# DAP-Audio-1.net
KiCad netlist of a schematic drawn in Altium Designer
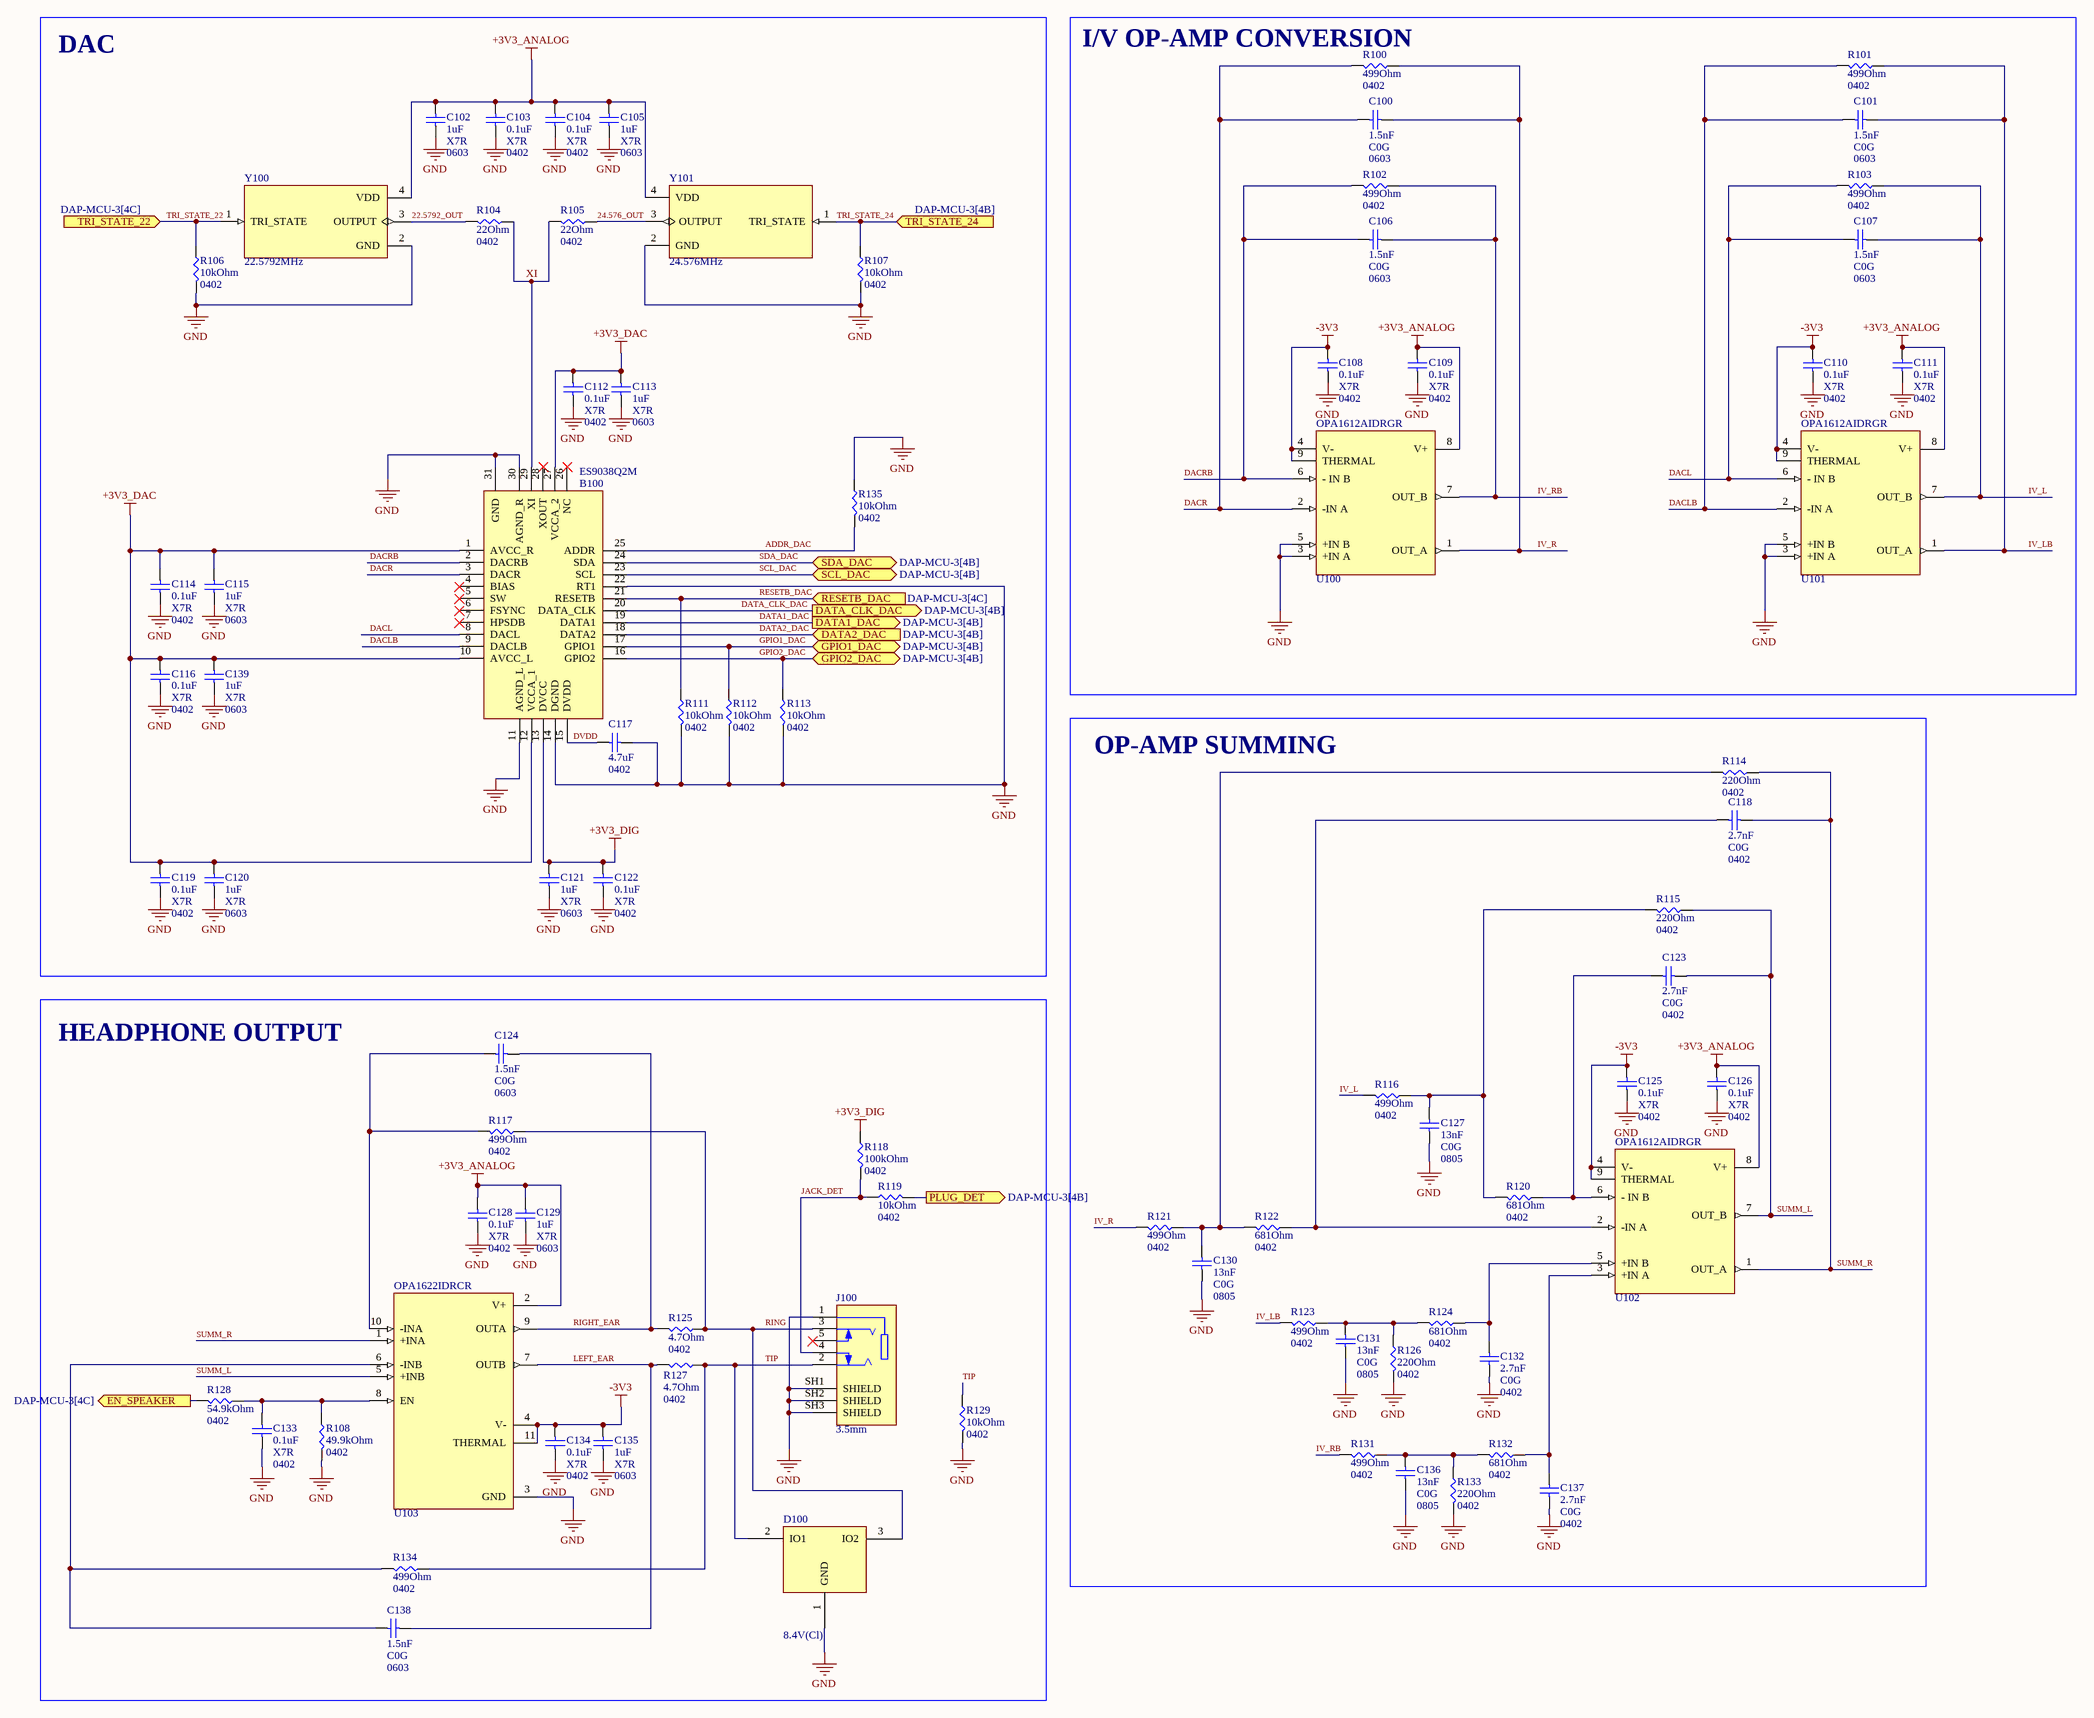
[diagram p0: DAP-Audio-1.SchDoc]

(export (version "E")
  (design (tool "Eeschema 10.0.6"))
  (components
    (comp (ref "B100")
      (value "DAC Audiophile")
      (footprint "QFN40P300X500X80-31N-D")
      (fields
        (field (name "MOUSER PART NUMBER") "460-ES9038Q2M")
        (field (name "MANUFACTURER_PART_NUMBER") "ES9038Q2M")
        (field (name "MANUFACTURER PART NUMBER 1") "ES9038Q2M")
        (field (name "CREATOR PROJECT") "DAP")
      )
      (libsource (lib "aloker-Link") (part "ES9038Q2M"))
    )
    (comp (ref "C100")
      (value "CAP CER 1500PF 50V C0G/NP0 0603")
      (footprint "CAPC1608X100N")
      (fields
        (field (name "<VALUE>") "1.5nF")
        (field (name "<SPEC>") "C0G")
        (field (name "<FOOTPRINT>") "0603")
        (field (name "CREATOR PROJECT") "DAP")
      )
      (libsource (lib "aloker-Link") (part "CAP"))
    )
    (comp (ref "C101")
      (value "CAP CER 1500PF 50V C0G/NP0 0603")
      (footprint "CAPC1608X100N")
      (fields
        (field (name "<VALUE>") "1.5nF")
        (field (name "<SPEC>") "C0G")
        (field (name "<FOOTPRINT>") "0603")
        (field (name "CREATOR PROJECT") "DAP")
      )
      (libsource (lib "aloker-Link") (part "CAP"))
    )
    (comp (ref "C102")
      (value "CAP CER 1UF 25V X7R 0603")
      (footprint "CAPC1608X100N")
      (fields
        (field (name "<VALUE>") "1uF")
        (field (name "<SPEC>") "X7R")
        (field (name "<FOOTPRINT>") "0603")
        (field (name "CREATOR PROJECT") "DAP")
      )
      (libsource (lib "aloker-Link") (part "CAP"))
    )
    (comp (ref "C103")
      (value "CAP CER 0.1UF 50V X7R 0402")
      (footprint "CAPC1005X60N")
      (fields
        (field (name "<VALUE>") "0.1uF")
        (field (name "<SPEC>") "X7R")
        (field (name "<FOOTPRINT>") "0402")
        (field (name "CREATOR PROJECT") "DAP")
      )
      (libsource (lib "aloker-Link") (part "CAP"))
    )
    (comp (ref "C104")
      (value "CAP CER 0.1UF 50V X7R 0402")
      (footprint "CAPC1005X60N")
      (fields
        (field (name "<VALUE>") "0.1uF")
        (field (name "<SPEC>") "X7R")
        (field (name "<FOOTPRINT>") "0402")
        (field (name "CREATOR PROJECT") "DAP")
      )
      (libsource (lib "aloker-Link") (part "CAP"))
    )
    (comp (ref "C105")
      (value "CAP CER 1UF 25V X7R 0603")
      (footprint "CAPC1608X100N")
      (fields
        (field (name "<VALUE>") "1uF")
        (field (name "<SPEC>") "X7R")
        (field (name "<FOOTPRINT>") "0603")
        (field (name "CREATOR PROJECT") "DAP")
      )
      (libsource (lib "aloker-Link") (part "CAP"))
    )
    (comp (ref "C106")
      (value "CAP CER 1500PF 50V C0G/NP0 0603")
      (footprint "CAPC1608X100N")
      (fields
        (field (name "<VALUE>") "1.5nF")
        (field (name "<SPEC>") "C0G")
        (field (name "<FOOTPRINT>") "0603")
        (field (name "CREATOR PROJECT") "DAP")
      )
      (libsource (lib "aloker-Link") (part "CAP"))
    )
    (comp (ref "C107")
      (value "CAP CER 1500PF 50V C0G/NP0 0603")
      (footprint "CAPC1608X100N")
      (fields
        (field (name "<VALUE>") "1.5nF")
        (field (name "<SPEC>") "C0G")
        (field (name "<FOOTPRINT>") "0603")
        (field (name "CREATOR PROJECT") "DAP")
      )
      (libsource (lib "aloker-Link") (part "CAP"))
    )
    (comp (ref "C108")
      (value "CAP CER 0.1UF 50V X7R 0402")
      (footprint "CAPC1005X60N")
      (fields
        (field (name "<VALUE>") "0.1uF")
        (field (name "<SPEC>") "X7R")
        (field (name "<FOOTPRINT>") "0402")
        (field (name "CREATOR PROJECT") "DAP")
      )
      (libsource (lib "aloker-Link") (part "CAP"))
    )
    (comp (ref "C109")
      (value "CAP CER 0.1UF 50V X7R 0402")
      (footprint "CAPC1005X60N")
      (fields
        (field (name "<VALUE>") "0.1uF")
        (field (name "<SPEC>") "X7R")
        (field (name "<FOOTPRINT>") "0402")
        (field (name "CREATOR PROJECT") "DAP")
      )
      (libsource (lib "aloker-Link") (part "CAP"))
    )
    (comp (ref "C110")
      (value "CAP CER 0.1UF 50V X7R 0402")
      (footprint "CAPC1005X60N")
      (fields
        (field (name "<VALUE>") "0.1uF")
        (field (name "<SPEC>") "X7R")
        (field (name "<FOOTPRINT>") "0402")
        (field (name "CREATOR PROJECT") "DAP")
      )
      (libsource (lib "aloker-Link") (part "CAP"))
    )
    (comp (ref "C111")
      (value "CAP CER 0.1UF 50V X7R 0402")
      (footprint "CAPC1005X60N")
      (fields
        (field (name "<VALUE>") "0.1uF")
        (field (name "<SPEC>") "X7R")
        (field (name "<FOOTPRINT>") "0402")
        (field (name "CREATOR PROJECT") "DAP")
      )
      (libsource (lib "aloker-Link") (part "CAP"))
    )
    (comp (ref "C112")
      (value "CAP CER 0.1UF 50V X7R 0402")
      (footprint "CAPC1005X60N")
      (fields
        (field (name "<VALUE>") "0.1uF")
        (field (name "<SPEC>") "X7R")
        (field (name "<FOOTPRINT>") "0402")
        (field (name "CREATOR PROJECT") "DAP")
      )
      (libsource (lib "aloker-Link") (part "CAP"))
    )
    (comp (ref "C113")
      (value "CAP CER 1UF 25V X7R 0603")
      (footprint "CAPC1608X100N")
      (fields
        (field (name "<VALUE>") "1uF")
        (field (name "<SPEC>") "X7R")
        (field (name "<FOOTPRINT>") "0603")
        (field (name "CREATOR PROJECT") "DAP")
      )
      (libsource (lib "aloker-Link") (part "CAP"))
    )
    (comp (ref "C114")
      (value "CAP CER 0.1UF 50V X7R 0402")
      (footprint "CAPC1005X60N")
      (fields
        (field (name "<VALUE>") "0.1uF")
        (field (name "<SPEC>") "X7R")
        (field (name "<FOOTPRINT>") "0402")
        (field (name "CREATOR PROJECT") "DAP")
      )
      (libsource (lib "aloker-Link") (part "CAP"))
    )
    (comp (ref "C115")
      (value "CAP CER 1UF 25V X7R 0603")
      (footprint "CAPC1608X100N")
      (fields
        (field (name "<VALUE>") "1uF")
        (field (name "<SPEC>") "X7R")
        (field (name "<FOOTPRINT>") "0603")
        (field (name "CREATOR PROJECT") "DAP")
      )
      (libsource (lib "aloker-Link") (part "CAP"))
    )
    (comp (ref "C116")
      (value "CAP CER 0.1UF 50V X7R 0402")
      (footprint "CAPC1005X60N")
      (fields
        (field (name "<VALUE>") "0.1uF")
        (field (name "<SPEC>") "X7R")
        (field (name "<FOOTPRINT>") "0402")
        (field (name "CREATOR PROJECT") "DAP")
      )
      (libsource (lib "aloker-Link") (part "CAP"))
    )
    (comp (ref "C117")
      (value "CAP CER 4.7UF 6.3V X5R 0402")
      (footprint "CAPC1005X60N")
      (fields
        (field (name "<VALUE>") "4.7uF")
        (field (name "<FOOTPRINT>") "0402")
        (field (name "CREATOR PROJECT") "DAP")
      )
      (libsource (lib "aloker-Link") (part "CAP"))
    )
    (comp (ref "C118")
      (value "CAP CER 2700PF 50V C0G/NP0 0402")
      (footprint "CAPC1005X60N")
      (fields
        (field (name "<VALUE>") "2.7nF")
        (field (name "<SPEC>") "C0G")
        (field (name "<FOOTPRINT>") "0402")
        (field (name "CREATOR PROJECT") "DAP")
      )
      (libsource (lib "aloker-Link") (part "CAP"))
    )
    (comp (ref "C119")
      (value "CAP CER 0.1UF 50V X7R 0402")
      (footprint "CAPC1005X60N")
      (fields
        (field (name "<VALUE>") "0.1uF")
        (field (name "<SPEC>") "X7R")
        (field (name "<FOOTPRINT>") "0402")
        (field (name "CREATOR PROJECT") "DAP")
      )
      (libsource (lib "aloker-Link") (part "CAP"))
    )
    (comp (ref "C120")
      (value "CAP CER 1UF 25V X7R 0603")
      (footprint "CAPC1608X100N")
      (fields
        (field (name "<VALUE>") "1uF")
        (field (name "<SPEC>") "X7R")
        (field (name "<FOOTPRINT>") "0603")
        (field (name "CREATOR PROJECT") "DAP")
      )
      (libsource (lib "aloker-Link") (part "CAP"))
    )
    (comp (ref "C121")
      (value "CAP CER 1UF 25V X7R 0603")
      (footprint "CAPC1608X100N")
      (fields
        (field (name "<VALUE>") "1uF")
        (field (name "<SPEC>") "X7R")
        (field (name "<FOOTPRINT>") "0603")
        (field (name "CREATOR PROJECT") "DAP")
      )
      (libsource (lib "aloker-Link") (part "CAP"))
    )
    (comp (ref "C122")
      (value "CAP CER 0.1UF 50V X7R 0402")
      (footprint "CAPC1005X60N")
      (fields
        (field (name "<VALUE>") "0.1uF")
        (field (name "<SPEC>") "X7R")
        (field (name "<FOOTPRINT>") "0402")
        (field (name "CREATOR PROJECT") "DAP")
      )
      (libsource (lib "aloker-Link") (part "CAP"))
    )
    (comp (ref "C123")
      (value "CAP CER 2700PF 50V C0G/NP0 0402")
      (footprint "CAPC1005X60N")
      (fields
        (field (name "<VALUE>") "2.7nF")
        (field (name "<SPEC>") "C0G")
        (field (name "<FOOTPRINT>") "0402")
        (field (name "CREATOR PROJECT") "DAP")
      )
      (libsource (lib "aloker-Link") (part "CAP"))
    )
    (comp (ref "C124")
      (value "CAP CER 1500PF 50V C0G/NP0 0603")
      (footprint "CAPC1608X100N")
      (fields
        (field (name "<VALUE>") "1.5nF")
        (field (name "<SPEC>") "C0G")
        (field (name "<FOOTPRINT>") "0603")
        (field (name "CREATOR PROJECT") "DAP")
      )
      (libsource (lib "aloker-Link") (part "CAP"))
    )
    (comp (ref "C125")
      (value "CAP CER 0.1UF 50V X7R 0402")
      (footprint "CAPC1005X60N")
      (fields
        (field (name "<VALUE>") "0.1uF")
        (field (name "<SPEC>") "X7R")
        (field (name "<FOOTPRINT>") "0402")
        (field (name "CREATOR PROJECT") "DAP")
      )
      (libsource (lib "aloker-Link") (part "CAP"))
    )
    (comp (ref "C126")
      (value "CAP CER 0.1UF 50V X7R 0402")
      (footprint "CAPC1005X60N")
      (fields
        (field (name "<VALUE>") "0.1uF")
        (field (name "<SPEC>") "X7R")
        (field (name "<FOOTPRINT>") "0402")
        (field (name "CREATOR PROJECT") "DAP")
      )
      (libsource (lib "aloker-Link") (part "CAP"))
    )
    (comp (ref "C127")
      (value "CAP CER 0.013UF 50V C0G/NP0 0805")
      (footprint "CAP_MUR_0805")
      (fields
        (field (name "<VALUE>") "13nF")
        (field (name "<SPEC>") "C0G")
        (field (name "<FOOTPRINT>") "0805")
        (field (name "CREATOR PROJECT") "DAP")
      )
      (libsource (lib "aloker-Link") (part "CAP"))
    )
    (comp (ref "C128")
      (value "CAP CER 0.1UF 50V X7R 0402")
      (footprint "CAPC1005X60N")
      (fields
        (field (name "<VALUE>") "0.1uF")
        (field (name "<SPEC>") "X7R")
        (field (name "<FOOTPRINT>") "0402")
        (field (name "CREATOR PROJECT") "DAP")
      )
      (libsource (lib "aloker-Link") (part "CAP"))
    )
    (comp (ref "C129")
      (value "CAP CER 1UF 25V X7R 0603")
      (footprint "CAPC1608X100N")
      (fields
        (field (name "<VALUE>") "1uF")
        (field (name "<SPEC>") "X7R")
        (field (name "<FOOTPRINT>") "0603")
        (field (name "CREATOR PROJECT") "DAP")
      )
      (libsource (lib "aloker-Link") (part "CAP"))
    )
    (comp (ref "C130")
      (value "CAP CER 0.013UF 50V C0G/NP0 0805")
      (footprint "CAP_MUR_0805")
      (fields
        (field (name "<VALUE>") "13nF")
        (field (name "<SPEC>") "C0G")
        (field (name "<FOOTPRINT>") "0805")
        (field (name "CREATOR PROJECT") "DAP")
      )
      (libsource (lib "aloker-Link") (part "CAP"))
    )
    (comp (ref "C131")
      (value "CAP CER 0.013UF 50V C0G/NP0 0805")
      (footprint "CAP_MUR_0805")
      (fields
        (field (name "<VALUE>") "13nF")
        (field (name "<SPEC>") "C0G")
        (field (name "<FOOTPRINT>") "0805")
        (field (name "CREATOR PROJECT") "DAP")
      )
      (libsource (lib "aloker-Link") (part "CAP"))
    )
    (comp (ref "C132")
      (value "CAP CER 2700PF 50V C0G/NP0 0402")
      (footprint "CAPC1005X60N")
      (fields
        (field (name "<VALUE>") "2.7nF")
        (field (name "<SPEC>") "C0G")
        (field (name "<FOOTPRINT>") "0402")
        (field (name "CREATOR PROJECT") "DAP")
      )
      (libsource (lib "aloker-Link") (part "CAP"))
    )
    (comp (ref "C133")
      (value "CAP CER 0.1UF 50V X7R 0402")
      (footprint "CAPC1005X60N")
      (fields
        (field (name "<VALUE>") "0.1uF")
        (field (name "<SPEC>") "X7R")
        (field (name "<FOOTPRINT>") "0402")
        (field (name "CREATOR PROJECT") "DAP")
      )
      (libsource (lib "aloker-Link") (part "CAP"))
    )
    (comp (ref "C134")
      (value "CAP CER 0.1UF 50V X7R 0402")
      (footprint "CAPC1005X60N")
      (fields
        (field (name "<VALUE>") "0.1uF")
        (field (name "<SPEC>") "X7R")
        (field (name "<FOOTPRINT>") "0402")
        (field (name "CREATOR PROJECT") "DAP")
      )
      (libsource (lib "aloker-Link") (part "CAP"))
    )
    (comp (ref "C135")
      (value "CAP CER 1UF 25V X7R 0603")
      (footprint "CAPC1608X100N")
      (fields
        (field (name "<VALUE>") "1uF")
        (field (name "<SPEC>") "X7R")
        (field (name "<FOOTPRINT>") "0603")
        (field (name "CREATOR PROJECT") "DAP")
      )
      (libsource (lib "aloker-Link") (part "CAP"))
    )
    (comp (ref "C136")
      (value "CAP CER 0.013UF 50V C0G/NP0 0805")
      (footprint "CAP_MUR_0805")
      (fields
        (field (name "<VALUE>") "13nF")
        (field (name "<SPEC>") "C0G")
        (field (name "<FOOTPRINT>") "0805")
        (field (name "CREATOR PROJECT") "DAP")
      )
      (libsource (lib "aloker-Link") (part "CAP"))
    )
    (comp (ref "C137")
      (value "CAP CER 2700PF 50V C0G/NP0 0402")
      (footprint "CAPC1005X60N")
      (fields
        (field (name "<VALUE>") "2.7nF")
        (field (name "<SPEC>") "C0G")
        (field (name "<FOOTPRINT>") "0402")
        (field (name "CREATOR PROJECT") "DAP")
      )
      (libsource (lib "aloker-Link") (part "CAP"))
    )
    (comp (ref "C138")
      (value "CAP CER 1500PF 50V C0G/NP0 0603")
      (footprint "CAPC1608X100N")
      (fields
        (field (name "<VALUE>") "1.5nF")
        (field (name "<SPEC>") "C0G")
        (field (name "<FOOTPRINT>") "0603")
        (field (name "CREATOR PROJECT") "DAP")
      )
      (libsource (lib "aloker-Link") (part "CAP"))
    )
    (comp (ref "C139")
      (value "CAP CER 1UF 25V X7R 0603")
      (footprint "CAPC1608X100N")
      (fields
        (field (name "<VALUE>") "1uF")
        (field (name "<SPEC>") "X7R")
        (field (name "<FOOTPRINT>") "0603")
        (field (name "CREATOR PROJECT") "DAP")
      )
      (libsource (lib "aloker-Link") (part "CAP"))
    )
    (comp (ref "D100")
      (value "TVS DIODE 3.6VWM 8.4VC 3X2SON")
      (footprint "IC_ESD122DMXR")
      (fields (field (name "<VALUE>") "8.4V(Cl)") (field (name "CREATOR PROJECT") "DAP"))
      (libsource (lib "aloker-Link") (part "TVS_DIODE_2BI"))
    )
    (comp (ref "J100")
      (value "CONN JACK STEREO 3.5MM R/A")
      (footprint "CUI_SJ1-3535NS")
      (fields
        (field (name "MF") "Same Sky")
        (field (name "MP") "SJ1-3535NS")
        (field (name "<VALUE>") "3.5mm")
        (field (name "CREATOR PROJECT") "DAP")
      )
      (libsource (lib "aloker-Link") (part "SJ1-3535NS"))
    )
    (comp (ref "R100")
      (value "RES SMD 499 OHM 0.1% 1/16W 0402")
      (footprint "RESC1005X40N")
      (fields
        (field (name "<VALUE>") "499Ohm")
        (field (name "<FOOTPRINT>") "0402")
        (field (name "CREATOR PROJECT") "DAP")
      )
      (libsource (lib "aloker-Link") (part "RES"))
    )
    (comp (ref "R101")
      (value "RES SMD 499 OHM 0.1% 1/16W 0402")
      (footprint "RESC1005X40N")
      (fields
        (field (name "<VALUE>") "499Ohm")
        (field (name "<FOOTPRINT>") "0402")
        (field (name "CREATOR PROJECT") "DAP")
      )
      (libsource (lib "aloker-Link") (part "RES"))
    )
    (comp (ref "R102")
      (value "RES SMD 499 OHM 0.1% 1/16W 0402")
      (footprint "RESC1005X40N")
      (fields
        (field (name "<VALUE>") "499Ohm")
        (field (name "<FOOTPRINT>") "0402")
        (field (name "CREATOR PROJECT") "DAP")
      )
      (libsource (lib "aloker-Link") (part "RES"))
    )
    (comp (ref "R103")
      (value "RES SMD 499 OHM 0.1% 1/16W 0402")
      (footprint "RESC1005X40N")
      (fields
        (field (name "<VALUE>") "499Ohm")
        (field (name "<FOOTPRINT>") "0402")
        (field (name "CREATOR PROJECT") "DAP")
      )
      (libsource (lib "aloker-Link") (part "RES"))
    )
    (comp (ref "R104")
      (value "RES 22 OHM 1% 1/16W 0402")
      (footprint "RESC1005X40N")
      (fields
        (field (name "<VALUE>") "22Ohm")
        (field (name "<FOOTPRINT>") "0402")
        (field (name "CREATOR PROJECT") "DAP")
      )
      (libsource (lib "aloker-Link") (part "RES"))
    )
    (comp (ref "R105")
      (value "RES 22 OHM 1% 1/16W 0402")
      (footprint "RESC1005X40N")
      (fields
        (field (name "<VALUE>") "22Ohm")
        (field (name "<FOOTPRINT>") "0402")
        (field (name "CREATOR PROJECT") "DAP")
      )
      (libsource (lib "aloker-Link") (part "RES"))
    )
    (comp (ref "R106")
      (value "RES SMD 10K OHM 1% 1/16W 0402")
      (footprint "RESC1005X40N")
      (fields
        (field (name "<VALUE>") "10kOhm")
        (field (name "<FOOTPRINT>") "0402")
        (field (name "CREATOR PROJECT") "DAP")
      )
      (libsource (lib "aloker-Link") (part "RES"))
    )
    (comp (ref "R107")
      (value "RES SMD 10K OHM 1% 1/16W 0402")
      (footprint "RESC1005X40N")
      (fields
        (field (name "<VALUE>") "10kOhm")
        (field (name "<FOOTPRINT>") "0402")
        (field (name "CREATOR PROJECT") "DAP")
      )
      (libsource (lib "aloker-Link") (part "RES"))
    )
    (comp (ref "R108")
      (value "RES SMD 49.9KOHM 0.1% 1/16W 0402")
      (footprint "RESC1005X40N")
      (fields
        (field (name "<VALUE>") "49.9kOhm")
        (field (name "<FOOTPRINT>") "0402")
        (field (name "CREATOR PROJECT") "DAP")
      )
      (libsource (lib "aloker-Link") (part "RES"))
    )
    (comp (ref "R111")
      (value "RES SMD 10K OHM 1% 1/16W 0402")
      (footprint "RESC1005X40N")
      (fields
        (field (name "<VALUE>") "10kOhm")
        (field (name "<FOOTPRINT>") "0402")
        (field (name "CREATOR PROJECT") "DAP")
      )
      (libsource (lib "aloker-Link") (part "RES"))
    )
    (comp (ref "R112")
      (value "RES SMD 10K OHM 1% 1/16W 0402")
      (footprint "RESC1005X40N")
      (fields
        (field (name "<VALUE>") "10kOhm")
        (field (name "<FOOTPRINT>") "0402")
        (field (name "CREATOR PROJECT") "DAP")
      )
      (libsource (lib "aloker-Link") (part "RES"))
    )
    (comp (ref "R113")
      (value "RES SMD 10K OHM 1% 1/16W 0402")
      (footprint "RESC1005X40N")
      (fields
        (field (name "<VALUE>") "10kOhm")
        (field (name "<FOOTPRINT>") "0402")
        (field (name "CREATOR PROJECT") "DAP")
      )
      (libsource (lib "aloker-Link") (part "RES"))
    )
    (comp (ref "R114")
      (value "RES SMD 220 OHM 0.1% 1/16W 0402")
      (footprint "RESC1005X40N")
      (fields
        (field (name "<VALUE>") "220Ohm")
        (field (name "<FOOTPRINT>") "0402")
        (field (name "CREATOR PROJECT") "DAP")
      )
      (libsource (lib "aloker-Link") (part "RES"))
    )
    (comp (ref "R115")
      (value "RES SMD 220 OHM 0.1% 1/16W 0402")
      (footprint "RESC1005X40N")
      (fields
        (field (name "<VALUE>") "220Ohm")
        (field (name "<FOOTPRINT>") "0402")
        (field (name "CREATOR PROJECT") "DAP")
      )
      (libsource (lib "aloker-Link") (part "RES"))
    )
    (comp (ref "R116")
      (value "RES SMD 499 OHM 0.1% 1/16W 0402")
      (footprint "RESC1005X40N")
      (fields
        (field (name "<VALUE>") "499Ohm")
        (field (name "<FOOTPRINT>") "0402")
        (field (name "CREATOR PROJECT") "DAP")
      )
      (libsource (lib "aloker-Link") (part "RES"))
    )
    (comp (ref "R117")
      (value "RES SMD 499 OHM 0.1% 1/16W 0402")
      (footprint "RESC1005X40N")
      (fields
        (field (name "<VALUE>") "499Ohm")
        (field (name "<FOOTPRINT>") "0402")
        (field (name "CREATOR PROJECT") "DAP")
      )
      (libsource (lib "aloker-Link") (part "RES"))
    )
    (comp (ref "R118")
      (value "RES SMD 100K OHM 0.1% 1/16W 0402")
      (footprint "RESC1005X40N")
      (fields
        (field (name "<VALUE>") "100kOhm")
        (field (name "<FOOTPRINT>") "0402")
        (field (name "CREATOR PROJECT") "DAP")
      )
      (libsource (lib "aloker-Link") (part "RES"))
    )
    (comp (ref "R119")
      (value "RES SMD 10K OHM 1% 1/16W 0402")
      (footprint "RESC1005X40N")
      (fields
        (field (name "<VALUE>") "10kOhm")
        (field (name "<FOOTPRINT>") "0402")
        (field (name "CREATOR PROJECT") "DAP")
      )
      (libsource (lib "aloker-Link") (part "RES"))
    )
    (comp (ref "R120")
      (value "RES SMD 681 OHM 0.1% 1/16W 0402")
      (footprint "RESC1005X40N")
      (fields
        (field (name "<VALUE>") "681Ohm")
        (field (name "<FOOTPRINT>") "0402")
        (field (name "CREATOR PROJECT") "DAP")
      )
      (libsource (lib "aloker-Link") (part "RES"))
    )
    (comp (ref "R121")
      (value "RES SMD 499 OHM 0.1% 1/16W 0402")
      (footprint "RESC1005X40N")
      (fields
        (field (name "<VALUE>") "499Ohm")
        (field (name "<FOOTPRINT>") "0402")
        (field (name "CREATOR PROJECT") "DAP")
      )
      (libsource (lib "aloker-Link") (part "RES"))
    )
    (comp (ref "R122")
      (value "RES SMD 681 OHM 0.1% 1/16W 0402")
      (footprint "RESC1005X40N")
      (fields
        (field (name "<VALUE>") "681Ohm")
        (field (name "<FOOTPRINT>") "0402")
        (field (name "CREATOR PROJECT") "DAP")
      )
      (libsource (lib "aloker-Link") (part "RES"))
    )
    (comp (ref "R123")
      (value "RES SMD 499 OHM 0.1% 1/16W 0402")
      (footprint "RESC1005X40N")
      (fields
        (field (name "<VALUE>") "499Ohm")
        (field (name "<FOOTPRINT>") "0402")
        (field (name "CREATOR PROJECT") "DAP")
      )
      (libsource (lib "aloker-Link") (part "RES"))
    )
    (comp (ref "R124")
      (value "RES SMD 681 OHM 0.1% 1/16W 0402")
      (footprint "RESC1005X40N")
      (fields
        (field (name "<VALUE>") "681Ohm")
        (field (name "<FOOTPRINT>") "0402")
        (field (name "CREATOR PROJECT") "DAP")
      )
      (libsource (lib "aloker-Link") (part "RES"))
    )
    (comp (ref "R125")
      (value "RES SMD 4.7 OHM 0.1% 1/16W 0402")
      (footprint "RESC1005X40N")
      (fields
        (field (name "<VALUE>") "4.7Ohm")
        (field (name "<FOOTPRINT>") "0402")
        (field (name "CREATOR PROJECT") "DAP")
      )
      (libsource (lib "aloker-Link") (part "RES"))
    )
    (comp (ref "R126")
      (value "RES SMD 220 OHM 0.1% 1/16W 0402")
      (footprint "RESC1005X40N")
      (fields
        (field (name "<VALUE>") "220Ohm")
        (field (name "<FOOTPRINT>") "0402")
        (field (name "CREATOR PROJECT") "DAP")
      )
      (libsource (lib "aloker-Link") (part "RES"))
    )
    (comp (ref "R127")
      (value "RES SMD 4.7 OHM 0.1% 1/16W 0402")
      (footprint "RESC1005X40N")
      (fields
        (field (name "<VALUE>") "4.7Ohm")
        (field (name "<FOOTPRINT>") "0402")
        (field (name "CREATOR PROJECT") "DAP")
      )
      (libsource (lib "aloker-Link") (part "RES"))
    )
    (comp (ref "R128")
      (value "RES SMD 54.9KOHM 0.1% 1/16W 0402")
      (footprint "RESC1005X40N")
      (fields
        (field (name "<VALUE>") "54.9kOhm")
        (field (name "<FOOTPRINT>") "0402")
        (field (name "CREATOR PROJECT") "DAP")
      )
      (libsource (lib "aloker-Link") (part "RES"))
    )
    (comp (ref "R129")
      (value "RES SMD 10K OHM 1% 1/16W 0402")
      (footprint "RESC1005X40N")
      (fields
        (field (name "<VALUE>") "10kOhm")
        (field (name "<FOOTPRINT>") "0402")
        (field (name "CREATOR PROJECT") "DAP")
      )
      (libsource (lib "aloker-Link") (part "RES"))
    )
    (comp (ref "R131")
      (value "RES SMD 499 OHM 0.1% 1/16W 0402")
      (footprint "RESC1005X40N")
      (fields
        (field (name "<VALUE>") "499Ohm")
        (field (name "<FOOTPRINT>") "0402")
        (field (name "CREATOR PROJECT") "DAP")
      )
      (libsource (lib "aloker-Link") (part "RES"))
    )
    (comp (ref "R132")
      (value "RES SMD 681 OHM 0.1% 1/16W 0402")
      (footprint "RESC1005X40N")
      (fields
        (field (name "<VALUE>") "681Ohm")
        (field (name "<FOOTPRINT>") "0402")
        (field (name "CREATOR PROJECT") "DAP")
      )
      (libsource (lib "aloker-Link") (part "RES"))
    )
    (comp (ref "R133")
      (value "RES SMD 220 OHM 0.1% 1/16W 0402")
      (footprint "RESC1005X40N")
      (fields
        (field (name "<VALUE>") "220Ohm")
        (field (name "<FOOTPRINT>") "0402")
        (field (name "CREATOR PROJECT") "DAP")
      )
      (libsource (lib "aloker-Link") (part "RES"))
    )
    (comp (ref "R134")
      (value "RES SMD 499 OHM 0.1% 1/16W 0402")
      (footprint "RESC1005X40N")
      (fields
        (field (name "<VALUE>") "499Ohm")
        (field (name "<FOOTPRINT>") "0402")
        (field (name "CREATOR PROJECT") "DAP")
      )
      (libsource (lib "aloker-Link") (part "RES"))
    )
    (comp (ref "R135")
      (value "RES SMD 10K OHM 1% 1/16W 0402")
      (footprint "RESC1005X40N")
      (fields
        (field (name "<VALUE>") "10kOhm")
        (field (name "<FOOTPRINT>") "0402")
        (field (name "CREATOR PROJECT") "DAP")
      )
      (libsource (lib "aloker-Link") (part "RES"))
    )
    (comp (ref "U100")
      (value "IC OP AMP 2CH 8-SON")
      (footprint "SON50P300X300X80-9N200X120")
      (fields
        (field (name "MANUFACTURER PART NUMBER 1") "OPA1612AIDRGR")
        (field (name "CREATOR PROJECT") "DAP")
      )
      (libsource (lib "aloker-Link") (part "OPA1612AIDRGR"))
    )
    (comp (ref "U101")
      (value "IC OP AMP 2CH 8-SON")
      (footprint "SON50P300X300X80-9N200X120")
      (fields
        (field (name "MANUFACTURER PART NUMBER 1") "OPA1612AIDRGR")
        (field (name "CREATOR PROJECT") "DAP")
      )
      (libsource (lib "aloker-Link") (part "OPA1612AIDRGR"))
    )
    (comp (ref "U102")
      (value "IC OP AMP 2CH 8-SON")
      (footprint "SON50P300X300X80-9N200X120")
      (fields
        (field (name "MANUFACTURER PART NUMBER 1") "OPA1612AIDRGR")
        (field (name "CREATOR PROJECT") "DAP")
      )
      (libsource (lib "aloker-Link") (part "OPA1612AIDRGR"))
    )
    (comp (ref "U103")
      (value "IC OP AMP 2CH 10-VSON")
      (footprint "IC_OPA1622IDRCR")
      (fields
        (field (name "MF") "Texas Instruments")
        (field (name "MP") "OPA1622IDRCR")
        (field (name "MANUFACTURER PART NUMBER 1") "OPA1622IDRCR")
        (field (name "CREATOR PROJECT") "DAP")
      )
      (libsource (lib "aloker-Link") (part "OPA1622IDRCR"))
    )
    (comp (ref "Y100")
      (value "XTAL OSC XO 22.5792MHZ CMOS SMD")
      (footprint "OSC_ECS-2520MVLC-225.792-CN-TR")
      (fields
        (field (name "MP") "ASTX-H11-24.576MHZ-T")
        (field (name "<VALUE>") "22.5792MHz")
        (field (name "CREATOR PROJECT") "DAP")
      )
      (libsource (lib "aloker-Link") (part "OSCILLATOR_CRYST_TRI"))
    )
    (comp (ref "Y101")
      (value "XTAL OSC TCXO 24.5760MHZ HCMOS")
      (footprint "XTAL_ASTX-H11-24.576MHZ-T")
      (fields
        (field (name "MP") "ASTX-H11-24.576MHZ-T")
        (field (name "<VALUE>") "24.576MHz")
        (field (name "CREATOR PROJECT") "DAP")
      )
      (libsource (lib "") (part "OSCILLATOR_CRYST_TRI_1"))
    )
  )
  (nets
    (net (code "1") (name "+3V3_ANALOG") (class "Default")
      (node (ref "C102") (pin "2") (pinfunction "2_2") (pintype "passive"))
      (node (ref "C103") (pin "2") (pinfunction "2_2") (pintype "passive"))
      (node (ref "C104") (pin "2") (pinfunction "2_2") (pintype "passive"))
      (node (ref "C105") (pin "2") (pinfunction "2_2") (pintype "passive"))
      (node (ref "C109") (pin "2") (pinfunction "2_2") (pintype "passive"))
      (node (ref "C111") (pin "2") (pinfunction "2_2") (pintype "passive"))
      (node (ref "C126") (pin "2") (pinfunction "2_2") (pintype "passive"))
      (node (ref "C128") (pin "2") (pinfunction "2_2") (pintype "passive"))
      (node (ref "C129") (pin "2") (pinfunction "2_2") (pintype "passive"))
      (node (ref "U100") (pin "8") (pinfunction "V+_8") (pintype "power_in"))
      (node (ref "U101") (pin "8") (pinfunction "V+_8") (pintype "power_in"))
      (node (ref "U102") (pin "8") (pinfunction "V+_8") (pintype "power_in"))
      (node (ref "U103") (pin "2") (pinfunction "V+_2") (pintype "power_in"))
      (node (ref "Y100") (pin "4") (pinfunction "VDD_4") (pintype "power_in"))
      (node (ref "Y101") (pin "4") (pinfunction "VDD_4") (pintype "power_in"))
    )
    (net (code "2") (name "+3V3_DAC") (class "Default")
      (node (ref "B100") (pin "1") (pinfunction "AVCC_R_1") (pintype "passive"))
      (node (ref "B100") (pin "10") (pinfunction "AVCC_L_10") (pintype "passive"))
      (node (ref "B100") (pin "12") (pinfunction "VCCA_1_12") (pintype "passive"))
      (node (ref "B100") (pin "27") (pinfunction "VCCA_2_27") (pintype "passive"))
      (node (ref "C112") (pin "2") (pinfunction "2_2") (pintype "passive"))
      (node (ref "C113") (pin "2") (pinfunction "2_2") (pintype "passive"))
      (node (ref "C114") (pin "2") (pinfunction "2_2") (pintype "passive"))
      (node (ref "C115") (pin "2") (pinfunction "2_2") (pintype "passive"))
      (node (ref "C116") (pin "2") (pinfunction "2_2") (pintype "passive"))
      (node (ref "C119") (pin "2") (pinfunction "2_2") (pintype "passive"))
      (node (ref "C120") (pin "2") (pinfunction "2_2") (pintype "passive"))
      (node (ref "C139") (pin "2") (pinfunction "2_2") (pintype "passive"))
    )
    (net (code "3") (name "+3V3_DIG") (class "Default")
      (node (ref "B100") (pin "13") (pinfunction "DVCC_13") (pintype "passive"))
      (node (ref "C121") (pin "2") (pinfunction "2_2") (pintype "passive"))
      (node (ref "C122") (pin "2") (pinfunction "2_2") (pintype "passive"))
      (node (ref "R118") (pin "2") (pinfunction "2_2") (pintype "passive"))
    )
    (net (code "4") (name "-3V3") (class "Default")
      (node (ref "C108") (pin "2") (pinfunction "2_2") (pintype "passive"))
      (node (ref "C110") (pin "2") (pinfunction "2_2") (pintype "passive"))
      (node (ref "C125") (pin "2") (pinfunction "2_2") (pintype "passive"))
      (node (ref "C134") (pin "2") (pinfunction "2_2") (pintype "passive"))
      (node (ref "C135") (pin "2") (pinfunction "2_2") (pintype "passive"))
      (node (ref "U100") (pin "4") (pinfunction "V-_4") (pintype "power_in"))
      (node (ref "U100") (pin "9") (pinfunction "THERMAL_9") (pintype "power_in"))
      (node (ref "U101") (pin "4") (pinfunction "V-_4") (pintype "power_in"))
      (node (ref "U101") (pin "9") (pinfunction "THERMAL_9") (pintype "power_in"))
      (node (ref "U102") (pin "4") (pinfunction "V-_4") (pintype "power_in"))
      (node (ref "U102") (pin "9") (pinfunction "THERMAL_9") (pintype "power_in"))
      (node (ref "U103") (pin "11") (pinfunction "THERMAL_11") (pintype "passive"))
      (node (ref "U103") (pin "4") (pinfunction "V-_4") (pintype "power_in"))
    )
    (net (code "5") (name "/22.5792_OUT") (class "Default")
      (node (ref "R104") (pin "1") (pinfunction "1_1") (pintype "passive"))
      (node (ref "Y100") (pin "3") (pinfunction "OUTPUT_3") (pintype "output"))
    )
    (net (code "6") (name "/24.576_OUT") (class "Default")
      (node (ref "R105") (pin "2") (pinfunction "2_2") (pintype "passive"))
      (node (ref "Y101") (pin "3") (pinfunction "OUTPUT_3") (pintype "output"))
    )
    (net (code "7") (name "/ADDR_DAC") (class "Default")
      (node (ref "B100") (pin "25") (pinfunction "ADDR_25") (pintype "passive"))
      (node (ref "R135") (pin "1") (pinfunction "1_1") (pintype "passive"))
    )
    (net (code "8") (name "/DACL") (class "Default")
      (node (ref "B100") (pin "8") (pinfunction "DACL_8") (pintype "passive"))
      (node (ref "C107") (pin "2") (pinfunction "2_2") (pintype "passive"))
      (node (ref "R103") (pin "1") (pinfunction "1_1") (pintype "passive"))
      (node (ref "U101") (pin "6") (pinfunction "-_IN_B_6") (pintype "input"))
    )
    (net (code "9") (name "/DACLB") (class "Default")
      (node (ref "B100") (pin "9") (pinfunction "DACLB_9") (pintype "passive"))
      (node (ref "C101") (pin "2") (pinfunction "2_2") (pintype "passive"))
      (node (ref "R101") (pin "1") (pinfunction "1_1") (pintype "passive"))
      (node (ref "U101") (pin "2") (pinfunction "-IN_A_2") (pintype "input"))
    )
    (net (code "10") (name "/DACR") (class "Default")
      (node (ref "B100") (pin "3") (pinfunction "DACR_3") (pintype "passive"))
      (node (ref "C100") (pin "2") (pinfunction "2_2") (pintype "passive"))
      (node (ref "R100") (pin "1") (pinfunction "1_1") (pintype "passive"))
      (node (ref "U100") (pin "2") (pinfunction "-IN_A_2") (pintype "input"))
    )
    (net (code "11") (name "/DACRB") (class "Default")
      (node (ref "B100") (pin "2") (pinfunction "DACRB_2") (pintype "passive"))
      (node (ref "C106") (pin "2") (pinfunction "2_2") (pintype "passive"))
      (node (ref "R102") (pin "1") (pinfunction "1_1") (pintype "passive"))
      (node (ref "U100") (pin "6") (pinfunction "-_IN_B_6") (pintype "input"))
    )
    (net (code "12") (name "/DATA1_DAC") (class "Default")
      (node (ref "B100") (pin "19") (pinfunction "DATA1_19") (pintype "passive"))
    )
    (net (code "13") (name "/DATA2_DAC") (class "Default")
      (node (ref "B100") (pin "18") (pinfunction "DATA2_18") (pintype "passive"))
    )
    (net (code "14") (name "/DATA_CLK_DAC") (class "Default")
      (node (ref "B100") (pin "20") (pinfunction "DATA_CLK_20") (pintype "passive"))
    )
    (net (code "15") (name "/DVDD") (class "Default")
      (node (ref "B100") (pin "15") (pinfunction "DVDD_15") (pintype "passive"))
      (node (ref "C117") (pin "2") (pinfunction "2_2") (pintype "passive"))
    )
    (net (code "16") (name "/EN_SPEAKER") (class "Default")
      (node (ref "R128") (pin "1") (pinfunction "1_1") (pintype "passive"))
    )
    (net (code "17") (name "/GPIO1_DAC") (class "Default")
      (node (ref "B100") (pin "17") (pinfunction "GPIO1_17") (pintype "passive"))
      (node (ref "R112") (pin "2") (pinfunction "2_2") (pintype "passive"))
    )
    (net (code "18") (name "/GPIO2_DAC") (class "Default")
      (node (ref "B100") (pin "16") (pinfunction "GPIO2_16") (pintype "passive"))
      (node (ref "R113") (pin "2") (pinfunction "2_2") (pintype "passive"))
    )
    (net (code "19") (name "/IV_L") (class "Default")
      (node (ref "C107") (pin "1") (pinfunction "1_1") (pintype "passive"))
      (node (ref "R103") (pin "2") (pinfunction "2_2") (pintype "passive"))
      (node (ref "R116") (pin "1") (pinfunction "1_1") (pintype "passive"))
      (node (ref "U101") (pin "7") (pinfunction "OUT_B_7") (pintype "output"))
    )
    (net (code "20") (name "/IV_LB") (class "Default")
      (node (ref "C101") (pin "1") (pinfunction "1_1") (pintype "passive"))
      (node (ref "R101") (pin "2") (pinfunction "2_2") (pintype "passive"))
      (node (ref "R123") (pin "1") (pinfunction "1_1") (pintype "passive"))
      (node (ref "U101") (pin "1") (pinfunction "OUT_A_1") (pintype "output"))
    )
    (net (code "21") (name "/IV_R") (class "Default")
      (node (ref "C100") (pin "1") (pinfunction "1_1") (pintype "passive"))
      (node (ref "R100") (pin "2") (pinfunction "2_2") (pintype "passive"))
      (node (ref "R121") (pin "1") (pinfunction "1_1") (pintype "passive"))
      (node (ref "U100") (pin "1") (pinfunction "OUT_A_1") (pintype "output"))
    )
    (net (code "22") (name "/IV_RB") (class "Default")
      (node (ref "C106") (pin "1") (pinfunction "1_1") (pintype "passive"))
      (node (ref "R102") (pin "2") (pinfunction "2_2") (pintype "passive"))
      (node (ref "R131") (pin "1") (pinfunction "1_1") (pintype "passive"))
      (node (ref "U100") (pin "7") (pinfunction "OUT_B_7") (pintype "output"))
    )
    (net (code "23") (name "/JACK_DET") (class "Default")
      (node (ref "J100") (pin "4") (pinfunction "4_4") (pintype "passive"))
      (node (ref "R118") (pin "1") (pinfunction "1_1") (pintype "passive"))
      (node (ref "R119") (pin "2") (pinfunction "2_2") (pintype "passive"))
    )
    (net (code "24") (name "/LEFT_EAR") (class "Default")
      (node (ref "C138") (pin "1") (pinfunction "1_1") (pintype "passive"))
      (node (ref "R127") (pin "1") (pinfunction "1_1") (pintype "passive"))
      (node (ref "U103") (pin "7") (pinfunction "OUTB_7") (pintype "output"))
    )
    (net (code "25") (name "/PLUG_DET") (class "Default")
      (node (ref "R119") (pin "1") (pinfunction "1_1") (pintype "passive"))
    )
    (net (code "26") (name "/RESETB_DAC") (class "Default")
      (node (ref "B100") (pin "21") (pinfunction "RESETB_21") (pintype "passive"))
      (node (ref "R111") (pin "2") (pinfunction "2_2") (pintype "passive"))
    )
    (net (code "27") (name "/RIGHT_EAR") (class "Default")
      (node (ref "C124") (pin "1") (pinfunction "1_1") (pintype "passive"))
      (node (ref "R125") (pin "1") (pinfunction "1_1") (pintype "passive"))
      (node (ref "U103") (pin "9") (pinfunction "OUTA_9") (pintype "output"))
    )
    (net (code "28") (name "/RING") (class "Default")
      (node (ref "D100") (pin "3") (pinfunction "IO2_3") (pintype "passive"))
      (node (ref "J100") (pin "3") (pinfunction "3_3") (pintype "passive"))
      (node (ref "R117") (pin "2") (pinfunction "2_2") (pintype "passive"))
      (node (ref "R125") (pin "2") (pinfunction "2_2") (pintype "passive"))
    )
    (net (code "29") (name "/SCL_DAC") (class "Default")
      (node (ref "B100") (pin "23") (pinfunction "SCL_23") (pintype "passive"))
    )
    (net (code "30") (name "/SDA_DAC") (class "Default")
      (node (ref "B100") (pin "24") (pinfunction "SDA_24") (pintype "passive"))
    )
    (net (code "31") (name "/SUMM_L") (class "Default")
      (node (ref "C123") (pin "1") (pinfunction "1_1") (pintype "passive"))
      (node (ref "R115") (pin "2") (pinfunction "2_2") (pintype "passive"))
      (node (ref "U102") (pin "7") (pinfunction "OUT_B_7") (pintype "output"))
      (node (ref "U103") (pin "5") (pinfunction "+INB_5") (pintype "input"))
    )
    (net (code "32") (name "/SUMM_R") (class "Default")
      (node (ref "C118") (pin "1") (pinfunction "1_1") (pintype "passive"))
      (node (ref "R114") (pin "2") (pinfunction "2_2") (pintype "passive"))
      (node (ref "U102") (pin "1") (pinfunction "OUT_A_1") (pintype "output"))
      (node (ref "U103") (pin "1") (pinfunction "+INA_1") (pintype "input"))
    )
    (net (code "33") (name "/TIP") (class "Default")
      (node (ref "D100") (pin "2") (pinfunction "IO1_2") (pintype "passive"))
      (node (ref "J100") (pin "2") (pinfunction "2_2") (pintype "passive"))
      (node (ref "R127") (pin "2") (pinfunction "2_2") (pintype "passive"))
      (node (ref "R129") (pin "2") (pinfunction "2_2") (pintype "passive"))
      (node (ref "R134") (pin "2") (pinfunction "2_2") (pintype "passive"))
    )
    (net (code "34") (name "/TRI_STATE_22") (class "Default")
      (node (ref "R106") (pin "2") (pinfunction "2_2") (pintype "passive"))
      (node (ref "Y100") (pin "1") (pinfunction "TRI_STATE_1") (pintype "input"))
    )
    (net (code "35") (name "/TRI_STATE_24") (class "Default")
      (node (ref "R107") (pin "2") (pinfunction "2_2") (pintype "passive"))
      (node (ref "Y101") (pin "1") (pinfunction "TRI_STATE_1") (pintype "input"))
    )
    (net (code "36") (name "/XI") (class "Default")
      (node (ref "B100") (pin "29") (pinfunction "XI_29") (pintype "passive"))
      (node (ref "R104") (pin "2") (pinfunction "2_2") (pintype "passive"))
      (node (ref "R105") (pin "1") (pinfunction "1_1") (pintype "passive"))
    )
    (net (code "37") (name "GND") (class "Default")
      (node (ref "B100") (pin "11") (pinfunction "AGND_L_11") (pintype "passive"))
      (node (ref "B100") (pin "14") (pinfunction "DGND_14") (pintype "passive"))
      (node (ref "B100") (pin "22") (pinfunction "RT1_22") (pintype "passive"))
      (node (ref "B100") (pin "30") (pinfunction "AGND_R_30") (pintype "passive"))
      (node (ref "B100") (pin "31") (pinfunction "GND_31") (pintype "passive"))
      (node (ref "C102") (pin "1") (pinfunction "1_1") (pintype "passive"))
      (node (ref "C103") (pin "1") (pinfunction "1_1") (pintype "passive"))
      (node (ref "C104") (pin "1") (pinfunction "1_1") (pintype "passive"))
      (node (ref "C105") (pin "1") (pinfunction "1_1") (pintype "passive"))
      (node (ref "C108") (pin "1") (pinfunction "1_1") (pintype "passive"))
      (node (ref "C109") (pin "1") (pinfunction "1_1") (pintype "passive"))
      (node (ref "C110") (pin "1") (pinfunction "1_1") (pintype "passive"))
      (node (ref "C111") (pin "1") (pinfunction "1_1") (pintype "passive"))
      (node (ref "C112") (pin "1") (pinfunction "1_1") (pintype "passive"))
      (node (ref "C113") (pin "1") (pinfunction "1_1") (pintype "passive"))
      (node (ref "C114") (pin "1") (pinfunction "1_1") (pintype "passive"))
      (node (ref "C115") (pin "1") (pinfunction "1_1") (pintype "passive"))
      (node (ref "C116") (pin "1") (pinfunction "1_1") (pintype "passive"))
      (node (ref "C117") (pin "1") (pinfunction "1_1") (pintype "passive"))
      (node (ref "C119") (pin "1") (pinfunction "1_1") (pintype "passive"))
      (node (ref "C120") (pin "1") (pinfunction "1_1") (pintype "passive"))
      (node (ref "C121") (pin "1") (pinfunction "1_1") (pintype "passive"))
      (node (ref "C122") (pin "1") (pinfunction "1_1") (pintype "passive"))
      (node (ref "C125") (pin "1") (pinfunction "1_1") (pintype "passive"))
      (node (ref "C126") (pin "1") (pinfunction "1_1") (pintype "passive"))
      (node (ref "C127") (pin "1") (pinfunction "1_1") (pintype "passive"))
      (node (ref "C128") (pin "1") (pinfunction "1_1") (pintype "passive"))
      (node (ref "C129") (pin "1") (pinfunction "1_1") (pintype "passive"))
      (node (ref "C130") (pin "1") (pinfunction "1_1") (pintype "passive"))
      (node (ref "C131") (pin "1") (pinfunction "1_1") (pintype "passive"))
      (node (ref "C132") (pin "2") (pinfunction "2_2") (pintype "passive"))
      (node (ref "C133") (pin "1") (pinfunction "1_1") (pintype "passive"))
      (node (ref "C134") (pin "1") (pinfunction "1_1") (pintype "passive"))
      (node (ref "C135") (pin "1") (pinfunction "1_1") (pintype "passive"))
      (node (ref "C136") (pin "1") (pinfunction "1_1") (pintype "passive"))
      (node (ref "C137") (pin "2") (pinfunction "2_2") (pintype "passive"))
      (node (ref "C139") (pin "1") (pinfunction "1_1") (pintype "passive"))
      (node (ref "D100") (pin "1") (pinfunction "GND_1") (pintype "passive"))
      (node (ref "J100") (pin "1") (pinfunction "1_1") (pintype "passive"))
      (node (ref "J100") (pin "SH1") (pinfunction "SHIELD_SH1") (pintype "passive"))
      (node (ref "J100") (pin "SH2") (pinfunction "SHIELD_SH2") (pintype "passive"))
      (node (ref "J100") (pin "SH3") (pinfunction "SHIELD_SH3") (pintype "passive"))
      (node (ref "R106") (pin "1") (pinfunction "1_1") (pintype "passive"))
      (node (ref "R107") (pin "1") (pinfunction "1_1") (pintype "passive"))
      (node (ref "R108") (pin "1") (pinfunction "1_1") (pintype "passive"))
      (node (ref "R111") (pin "1") (pinfunction "1_1") (pintype "passive"))
      (node (ref "R112") (pin "1") (pinfunction "1_1") (pintype "passive"))
      (node (ref "R113") (pin "1") (pinfunction "1_1") (pintype "passive"))
      (node (ref "R126") (pin "1") (pinfunction "1_1") (pintype "passive"))
      (node (ref "R129") (pin "1") (pinfunction "1_1") (pintype "passive"))
      (node (ref "R133") (pin "1") (pinfunction "1_1") (pintype "passive"))
      (node (ref "R135") (pin "2") (pinfunction "2_2") (pintype "passive"))
      (node (ref "U100") (pin "3") (pinfunction "+IN_A_3") (pintype "input"))
      (node (ref "U100") (pin "5") (pinfunction "+IN_B_5") (pintype "input"))
      (node (ref "U101") (pin "3") (pinfunction "+IN_A_3") (pintype "input"))
      (node (ref "U101") (pin "5") (pinfunction "+IN_B_5") (pintype "input"))
      (node (ref "U103") (pin "3") (pinfunction "GND_3") (pintype "power_in"))
      (node (ref "Y100") (pin "2") (pinfunction "GND_2") (pintype "power_in"))
      (node (ref "Y101") (pin "2") (pinfunction "GND_2") (pintype "power_in"))
    )
    (net (code "38") (name "Net-(C127-Pad2)") (class "Default")
      (node (ref "C127") (pin "2") (pinfunction "2_2") (pintype "passive"))
      (node (ref "R115") (pin "1") (pinfunction "1_1") (pintype "passive"))
      (node (ref "R116") (pin "2") (pinfunction "2_2") (pintype "passive"))
      (node (ref "R120") (pin "1") (pinfunction "1_1") (pintype "passive"))
    )
    (net (code "39") (name "Net-(C130-Pad2)") (class "Default")
      (node (ref "C130") (pin "2") (pinfunction "2_2") (pintype "passive"))
      (node (ref "R114") (pin "1") (pinfunction "1_1") (pintype "passive"))
      (node (ref "R121") (pin "2") (pinfunction "2_2") (pintype "passive"))
      (node (ref "R122") (pin "1") (pinfunction "1_1") (pintype "passive"))
    )
    (net (code "40") (name "Net-(C131-Pad2)") (class "Default")
      (node (ref "C131") (pin "2") (pinfunction "2_2") (pintype "passive"))
      (node (ref "R123") (pin "2") (pinfunction "2_2") (pintype "passive"))
      (node (ref "R124") (pin "1") (pinfunction "1_1") (pintype "passive"))
      (node (ref "R126") (pin "2") (pinfunction "2_2") (pintype "passive"))
    )
    (net (code "41") (name "Net-(C136-Pad2)") (class "Default")
      (node (ref "C136") (pin "2") (pinfunction "2_2") (pintype "passive"))
      (node (ref "R131") (pin "2") (pinfunction "2_2") (pintype "passive"))
      (node (ref "R132") (pin "1") (pinfunction "1_1") (pintype "passive"))
      (node (ref "R133") (pin "2") (pinfunction "2_2") (pintype "passive"))
    )
    (net (code "42") (name "Net-(U102-+IN_A)") (class "Default")
      (node (ref "C137") (pin "1") (pinfunction "1_1") (pintype "passive"))
      (node (ref "R132") (pin "2") (pinfunction "2_2") (pintype "passive"))
      (node (ref "U102") (pin "3") (pinfunction "+IN_A_3") (pintype "input"))
    )
    (net (code "43") (name "Net-(U102-+IN_B)") (class "Default")
      (node (ref "C132") (pin "1") (pinfunction "1_1") (pintype "passive"))
      (node (ref "R124") (pin "2") (pinfunction "2_2") (pintype "passive"))
      (node (ref "U102") (pin "5") (pinfunction "+IN_B_5") (pintype "input"))
    )
    (net (code "44") (name "Net-(U102--IN_A)") (class "Default")
      (node (ref "C118") (pin "2") (pinfunction "2_2") (pintype "passive"))
      (node (ref "R122") (pin "2") (pinfunction "2_2") (pintype "passive"))
      (node (ref "U102") (pin "2") (pinfunction "-IN_A_2") (pintype "input"))
    )
    (net (code "45") (name "Net-(U102--_IN_B)") (class "Default")
      (node (ref "C123") (pin "2") (pinfunction "2_2") (pintype "passive"))
      (node (ref "R120") (pin "2") (pinfunction "2_2") (pintype "passive"))
      (node (ref "U102") (pin "6") (pinfunction "-_IN_B_6") (pintype "input"))
    )
    (net (code "46") (name "Net-(U103--INA)") (class "Default")
      (node (ref "C124") (pin "2") (pinfunction "2_2") (pintype "passive"))
      (node (ref "R117") (pin "1") (pinfunction "1_1") (pintype "passive"))
      (node (ref "U103") (pin "10") (pinfunction "-INA_10") (pintype "input"))
    )
    (net (code "47") (name "Net-(U103--INB)") (class "Default")
      (node (ref "C138") (pin "2") (pinfunction "2_2") (pintype "passive"))
      (node (ref "R134") (pin "1") (pinfunction "1_1") (pintype "passive"))
      (node (ref "U103") (pin "6") (pinfunction "-INB_6") (pintype "input"))
    )
    (net (code "48") (name "Net-(U103-EN)") (class "Default")
      (node (ref "C133") (pin "2") (pinfunction "2_2") (pintype "passive"))
      (node (ref "R108") (pin "2") (pinfunction "2_2") (pintype "passive"))
      (node (ref "R128") (pin "2") (pinfunction "2_2") (pintype "passive"))
      (node (ref "U103") (pin "8") (pinfunction "EN_8") (pintype "input"))
    )
    (net (code "49") (name "unconnected-(B100-BIAS-Pad4)") (class "Default")
      (node (ref "B100") (pin "4") (pinfunction "BIAS_4") (pintype "passive+no_connect"))
    )
    (net (code "50") (name "unconnected-(B100-FSYNC-Pad6)") (class "Default")
      (node (ref "B100") (pin "6") (pinfunction "FSYNC_6") (pintype "passive+no_connect"))
    )
    (net (code "51") (name "unconnected-(B100-HPSDB-Pad7)") (class "Default")
      (node (ref "B100") (pin "7") (pinfunction "HPSDB_7") (pintype "passive+no_connect"))
    )
    (net (code "52") (name "unconnected-(B100-NC-Pad26)") (class "Default")
      (node (ref "B100") (pin "26") (pinfunction "NC_26") (pintype "passive+no_connect"))
    )
    (net (code "53") (name "unconnected-(B100-SW-Pad5)") (class "Default")
      (node (ref "B100") (pin "5") (pinfunction "SW_5") (pintype "passive+no_connect"))
    )
    (net (code "54") (name "unconnected-(B100-XOUT-Pad28)") (class "Default")
      (node (ref "B100") (pin "28") (pinfunction "XOUT_28") (pintype "passive+no_connect"))
    )
    (net (code "55") (name "unconnected-(J100-Pad5)") (class "Default")
      (node (ref "J100") (pin "5") (pinfunction "5_5") (pintype "passive+no_connect"))
    )
  )
)
